# V4-AddOnUigBeeSMD-V02-006.net
KiCad netlist of a schematic drawn in EAGLE
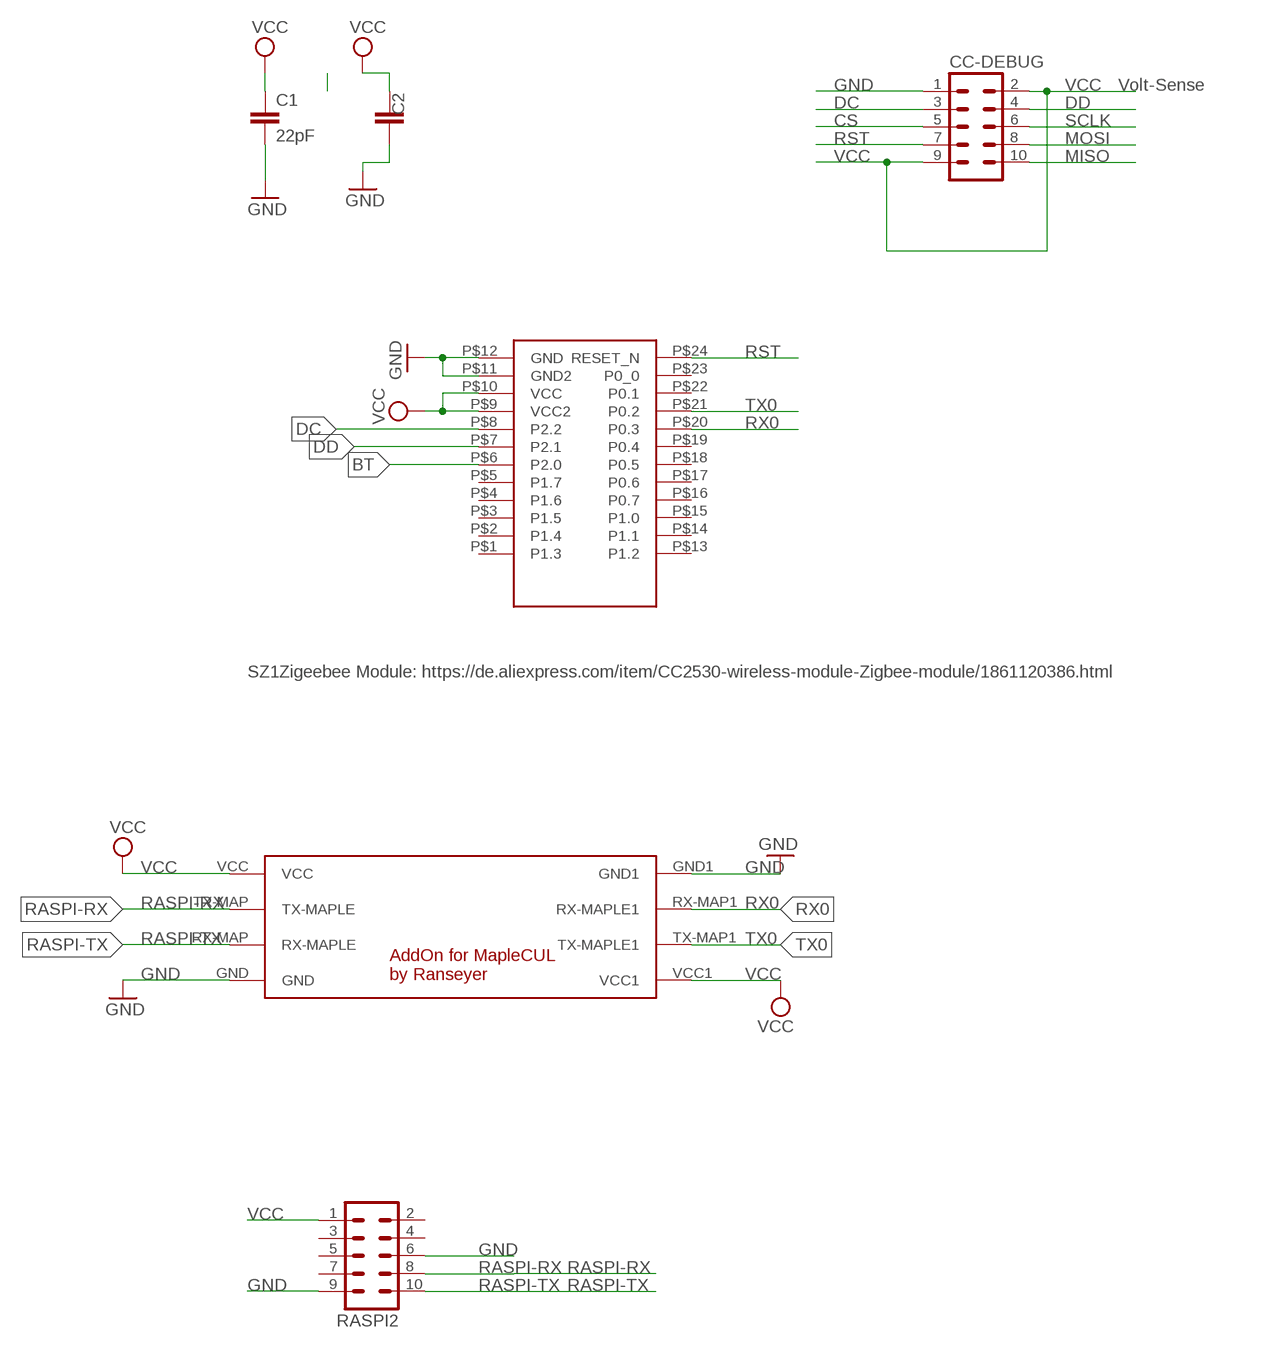
[diagram p0: schematic, sheet 1]

(export (version "E")
  (design (tool "Eeschema 10.0.6"))
  (components
    (comp (ref "C1")
      (value "22pF")
      (footprint "eagle-import:C0805")
      (libsource (lib "eagle-import") (part "C-EUC0805"))
    )
    (comp (ref "C2")
      (value "C-EUC1812")
      (footprint "eagle-import:C1812")
      (libsource (lib "eagle-import") (part "C-EUC1812"))
    )
    (comp (ref "CC-DEBUG")
      (value "CONN_05X2SHD_LOCK")
      (footprint "eagle-import:2X5-SHROUDED_LOCK")
      (libsource (lib "eagle-import") (part "CONN_05X2SHD_LOCK"))
    )
    (comp (ref "RASPI2")
      (value "MA05-2")
      (footprint "eagle-import:MA05-2")
      (libsource (lib "eagle-import") (part "MA05-2"))
    )
    (comp (ref "U$1")
      (value "MAPLE-CUL-ADDON-V01")
      (footprint "eagle-import:MAPLE-CUL-V01")
      (libsource (lib "eagle-import") (part "MAPLE-CUL-ADDON-V01"))
    )
    (comp (ref "U$2")
      (value "CC2530")
      (footprint "eagle-import:SZ1ZIGBEE-SMD")
      (libsource (lib "eagle-import") (part "CC2530"))
    )
  )
  (nets
    (net (code "1") (name "/CS") (class "Default")
      (node (ref "CC-DEBUG") (pin "5") (pinfunction "5_5") (pintype "passive"))
    )
    (net (code "2") (name "/MISO") (class "Default")
      (node (ref "CC-DEBUG") (pin "10") (pinfunction "10_10") (pintype "passive"))
    )
    (net (code "3") (name "/MOSI") (class "Default")
      (node (ref "CC-DEBUG") (pin "8") (pinfunction "8_8") (pintype "passive"))
    )
    (net (code "4") (name "/RST") (class "Default")
      (node (ref "CC-DEBUG") (pin "7") (pinfunction "7_7") (pintype "passive"))
      (node (ref "U$2") (pin "P$24") (pinfunction "RESET_N_P$24") (pintype "bidirectional"))
    )
    (net (code "5") (name "/SCLK") (class "Default")
      (node (ref "CC-DEBUG") (pin "6") (pinfunction "6_6") (pintype "passive"))
    )
    (net (code "6") (name "BT") (class "Default")
      (node (ref "U$2") (pin "P$6") (pinfunction "P2.0_P$6") (pintype "bidirectional"))
    )
    (net (code "7") (name "DC") (class "Default")
      (node (ref "CC-DEBUG") (pin "3") (pinfunction "3_3") (pintype "passive"))
      (node (ref "U$2") (pin "P$8") (pinfunction "P2.2_P$8") (pintype "bidirectional"))
    )
    (net (code "8") (name "DD") (class "Default")
      (node (ref "CC-DEBUG") (pin "4") (pinfunction "4_4") (pintype "passive"))
      (node (ref "U$2") (pin "P$7") (pinfunction "P2.1_P$7") (pintype "bidirectional"))
    )
    (net (code "9") (name "GND") (class "Default")
      (node (ref "C1") (pin "2") (pinfunction "2_2") (pintype "passive"))
      (node (ref "C2") (pin "1") (pinfunction "1_1") (pintype "passive"))
      (node (ref "CC-DEBUG") (pin "1") (pinfunction "1_1") (pintype "passive"))
      (node (ref "RASPI2") (pin "6") (pinfunction "6_6") (pintype "passive"))
      (node (ref "RASPI2") (pin "9") (pinfunction "9_9") (pintype "passive"))
      (node (ref "U$1") (pin "GND") (pinfunction "GND_GND") (pintype "bidirectional"))
      (node (ref "U$1") (pin "GND1") (pinfunction "GND1_GND1") (pintype "bidirectional"))
      (node (ref "U$2") (pin "P$11") (pinfunction "GND2_P$11") (pintype "bidirectional"))
      (node (ref "U$2") (pin "P$12") (pinfunction "GND_P$12") (pintype "bidirectional"))
    )
    (net (code "10") (name "RASPI-RX") (class "Default")
      (node (ref "RASPI2") (pin "8") (pinfunction "8_8") (pintype "passive"))
      (node (ref "U$1") (pin "TX-MAP") (pinfunction "TX-MAPLE_TX-MAP") (pintype "bidirectional"))
    )
    (net (code "11") (name "RASPI-TX") (class "Default")
      (node (ref "RASPI2") (pin "10") (pinfunction "10_10") (pintype "passive"))
      (node (ref "U$1") (pin "RX-MAP") (pinfunction "RX-MAPLE_RX-MAP") (pintype "bidirectional"))
    )
    (net (code "12") (name "RX0") (class "Default")
      (node (ref "U$1") (pin "RX-MAP1") (pinfunction "RX-MAPLE1_RX-MAP1") (pintype "bidirectional"))
      (node (ref "U$2") (pin "P$20") (pinfunction "P0.3_P$20") (pintype "bidirectional"))
    )
    (net (code "13") (name "TX0") (class "Default")
      (node (ref "U$1") (pin "TX-MAP1") (pinfunction "TX-MAPLE1_TX-MAP1") (pintype "bidirectional"))
      (node (ref "U$2") (pin "P$21") (pinfunction "P0.2_P$21") (pintype "bidirectional"))
    )
    (net (code "14") (name "VCC") (class "Default")
      (node (ref "C1") (pin "1") (pinfunction "1_1") (pintype "passive"))
      (node (ref "C2") (pin "2") (pinfunction "2_2") (pintype "passive"))
      (node (ref "CC-DEBUG") (pin "2") (pinfunction "2_2") (pintype "passive"))
      (node (ref "CC-DEBUG") (pin "9") (pinfunction "9_9") (pintype "passive"))
      (node (ref "RASPI2") (pin "1") (pinfunction "1_1") (pintype "passive"))
      (node (ref "U$1") (pin "VCC") (pinfunction "VCC_VCC") (pintype "bidirectional"))
      (node (ref "U$1") (pin "VCC1") (pinfunction "VCC1_VCC1") (pintype "bidirectional"))
      (node (ref "U$2") (pin "P$10") (pinfunction "VCC_P$10") (pintype "bidirectional"))
      (node (ref "U$2") (pin "P$9") (pinfunction "VCC2_P$9") (pintype "bidirectional"))
    )
    (net (code "15") (name "unconnected-(RASPI2-Pad2)") (class "Default")
      (node (ref "RASPI2") (pin "2") (pinfunction "2_2") (pintype "passive"))
    )
    (net (code "16") (name "unconnected-(RASPI2-Pad3)") (class "Default")
      (node (ref "RASPI2") (pin "3") (pinfunction "3_3") (pintype "passive"))
    )
    (net (code "17") (name "unconnected-(RASPI2-Pad4)") (class "Default")
      (node (ref "RASPI2") (pin "4") (pinfunction "4_4") (pintype "passive"))
    )
    (net (code "18") (name "unconnected-(RASPI2-Pad5)") (class "Default")
      (node (ref "RASPI2") (pin "5") (pinfunction "5_5") (pintype "passive"))
    )
    (net (code "19") (name "unconnected-(RASPI2-Pad7)") (class "Default")
      (node (ref "RASPI2") (pin "7") (pinfunction "7_7") (pintype "passive"))
    )
    (net (code "20") (name "unconnected-(U$2-P0.1-PadP$22)") (class "Default")
      (node (ref "U$2") (pin "P$22") (pinfunction "P0.1_P$22") (pintype "bidirectional"))
    )
    (net (code "21") (name "unconnected-(U$2-P0.4-PadP$19)") (class "Default")
      (node (ref "U$2") (pin "P$19") (pinfunction "P0.4_P$19") (pintype "bidirectional"))
    )
    (net (code "22") (name "unconnected-(U$2-P0.5-PadP$18)") (class "Default")
      (node (ref "U$2") (pin "P$18") (pinfunction "P0.5_P$18") (pintype "bidirectional"))
    )
    (net (code "23") (name "unconnected-(U$2-P0.6-PadP$17)") (class "Default")
      (node (ref "U$2") (pin "P$17") (pinfunction "P0.6_P$17") (pintype "bidirectional"))
    )
    (net (code "24") (name "unconnected-(U$2-P0.7-PadP$16)") (class "Default")
      (node (ref "U$2") (pin "P$16") (pinfunction "P0.7_P$16") (pintype "bidirectional"))
    )
    (net (code "25") (name "unconnected-(U$2-P0_0-PadP$23)") (class "Default")
      (node (ref "U$2") (pin "P$23") (pinfunction "P0_0_P$23") (pintype "bidirectional"))
    )
    (net (code "26") (name "unconnected-(U$2-P1.0-PadP$15)") (class "Default")
      (node (ref "U$2") (pin "P$15") (pinfunction "P1.0_P$15") (pintype "bidirectional"))
    )
    (net (code "27") (name "unconnected-(U$2-P1.1-PadP$14)") (class "Default")
      (node (ref "U$2") (pin "P$14") (pinfunction "P1.1_P$14") (pintype "bidirectional"))
    )
    (net (code "28") (name "unconnected-(U$2-P1.2-PadP$13)") (class "Default")
      (node (ref "U$2") (pin "P$13") (pinfunction "P1.2_P$13") (pintype "bidirectional"))
    )
    (net (code "29") (name "unconnected-(U$2-P1.3-PadP$1)") (class "Default")
      (node (ref "U$2") (pin "P$1") (pinfunction "P1.3_P$1") (pintype "bidirectional"))
    )
    (net (code "30") (name "unconnected-(U$2-P1.4-PadP$2)") (class "Default")
      (node (ref "U$2") (pin "P$2") (pinfunction "P1.4_P$2") (pintype "bidirectional"))
    )
    (net (code "31") (name "unconnected-(U$2-P1.5-PadP$3)") (class "Default")
      (node (ref "U$2") (pin "P$3") (pinfunction "P1.5_P$3") (pintype "bidirectional"))
    )
    (net (code "32") (name "unconnected-(U$2-P1.6-PadP$4)") (class "Default")
      (node (ref "U$2") (pin "P$4") (pinfunction "P1.6_P$4") (pintype "bidirectional"))
    )
    (net (code "33") (name "unconnected-(U$2-P1.7-PadP$5)") (class "Default")
      (node (ref "U$2") (pin "P$5") (pinfunction "P1.7_P$5") (pintype "bidirectional"))
    )
  )
)
